# connector-2channel.net
KiCad netlist of a schematic drawn in EAGLE
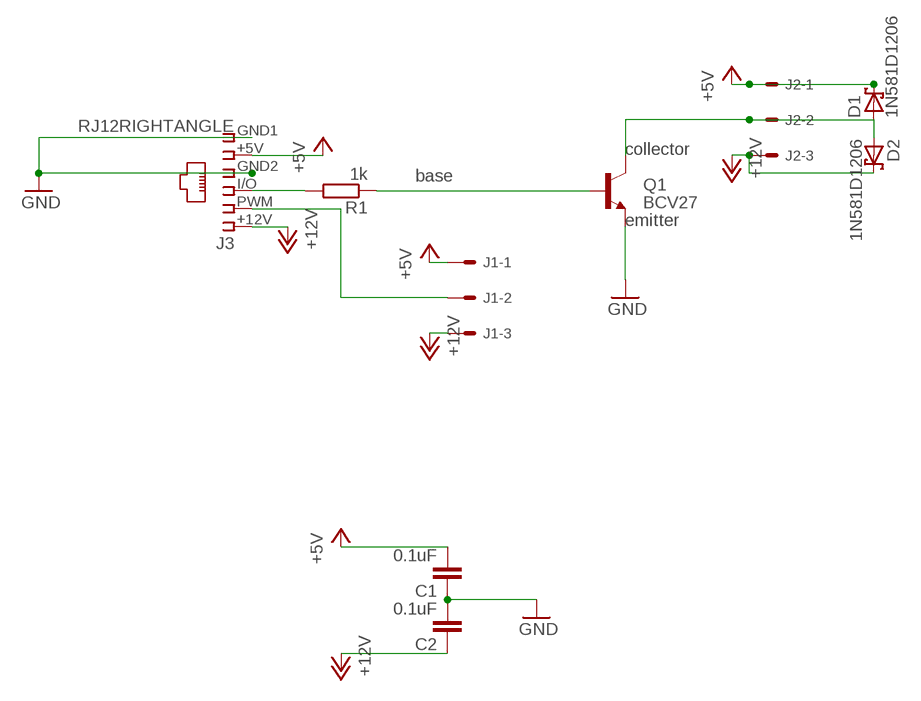
[diagram p0: schematic, sheet 1]

(export (version "E")
  (design (tool "Eeschema 10.0.6"))
  (components
    (comp (ref "C1")
      (value "0.1uF")
      (footprint "eagle-import:C1206")
      (libsource (lib "eagle-import") (part "C-EUC1206"))
    )
    (comp (ref "C2")
      (value "0.1uF")
      (footprint "eagle-import:C1206")
      (libsource (lib "eagle-import") (part "C-EUC1206"))
    )
    (comp (ref "D1")
      (value "1N581D1206")
      (footprint "eagle-import:LED-1206")
      (libsource (lib "eagle-import") (part "1N581D1206"))
    )
    (comp (ref "D2")
      (value "1N581D1206")
      (footprint "eagle-import:LED-1206")
      (libsource (lib "eagle-import") (part "1N581D1206"))
    )
    (comp (ref "J1")
      (value "22-27-2031-03")
      (footprint "eagle-import:6410-03")
      (libsource (lib "eagle-import") (part "22-?-0327-2031"))
    )
    (comp (ref "J2")
      (value "22-27-2031-03")
      (footprint "eagle-import:6410-03")
      (libsource (lib "eagle-import") (part "22-?-0327-2031"))
    )
    (comp (ref "J3")
      (value "RJ12RIGHTANGLE")
      (footprint "eagle-import:RJ12-RIGHTANGLE")
      (libsource (lib "eagle-import") (part "RJ12RIGHTANGLE"))
    )
    (comp (ref "Q1")
      (value "BCV27")
      (footprint "eagle-import:SOT23")
      (libsource (lib "eagle-import") (part "TRANSISTOR_NPNSOT23"))
    )
    (comp (ref "R1")
      (value "1k")
      (footprint "eagle-import:M1206")
      (libsource (lib "eagle-import") (part "R-EU_M1206"))
    )
  )
  (nets
    (net (code "1") (name "+5V") (class "Default")
      (node (ref "C1") (pin "2") (pinfunction "2_2") (pintype "passive"))
      (node (ref "D1") (pin "C") (pinfunction "C_C") (pintype "passive"))
      (node (ref "J1") (pin "1") (pinfunction "S_1") (pintype "passive"))
      (node (ref "J2") (pin "1") (pinfunction "S_1") (pintype "passive"))
      (node (ref "J3") (pin "+5V") (pinfunction "5_+5V") (pintype "bidirectional"))
    )
    (net (code "2") (name "+12V") (class "Default")
      (node (ref "C2") (pin "1") (pinfunction "1_1") (pintype "passive"))
      (node (ref "D2") (pin "C") (pinfunction "C_C") (pintype "passive"))
      (node (ref "J1") (pin "3") (pinfunction "S_3") (pintype "passive"))
      (node (ref "J2") (pin "3") (pinfunction "S_3") (pintype "passive"))
      (node (ref "J3") (pin "+12V") (pinfunction "1_+12V") (pintype "bidirectional"))
    )
    (net (code "3") (name "GND") (class "Default")
      (node (ref "C1") (pin "1") (pinfunction "1_1") (pintype "passive"))
      (node (ref "C2") (pin "2") (pinfunction "2_2") (pintype "passive"))
      (node (ref "J3") (pin "GND1") (pinfunction "6_GND1") (pintype "bidirectional"))
      (node (ref "J3") (pin "GND2") (pinfunction "4_GND2") (pintype "bidirectional"))
      (node (ref "Q1") (pin "2") (pinfunction "E_2") (pintype "passive"))
    )
    (net (code "4") (name "Net-(J1B-S)") (class "Default")
      (node (ref "J1") (pin "2") (pinfunction "S_2") (pintype "passive"))
      (node (ref "J3") (pin "PWM") (pinfunction "2_PWM") (pintype "bidirectional"))
    )
    (net (code "5") (name "Net-(J2B-S)") (class "Default")
      (node (ref "D1") (pin "A") (pinfunction "A_A") (pintype "passive"))
      (node (ref "D2") (pin "A") (pinfunction "A_A") (pintype "passive"))
      (node (ref "J2") (pin "2") (pinfunction "S_2") (pintype "passive"))
      (node (ref "Q1") (pin "3") (pinfunction "C_3") (pintype "passive"))
    )
    (net (code "6") (name "Net-(J3-3)") (class "Default")
      (node (ref "J3") (pin "I/O") (pinfunction "3_I/O") (pintype "bidirectional"))
      (node (ref "R1") (pin "2") (pinfunction "2_2") (pintype "passive"))
    )
    (net (code "7") (name "Net-(Q1-B)") (class "Default")
      (node (ref "Q1") (pin "1") (pinfunction "B_1") (pintype "passive"))
      (node (ref "R1") (pin "1") (pinfunction "1_1") (pintype "passive"))
    )
  )
)
